# Cutman-RevA.net
KiCad netlist of a schematic drawn in EAGLE
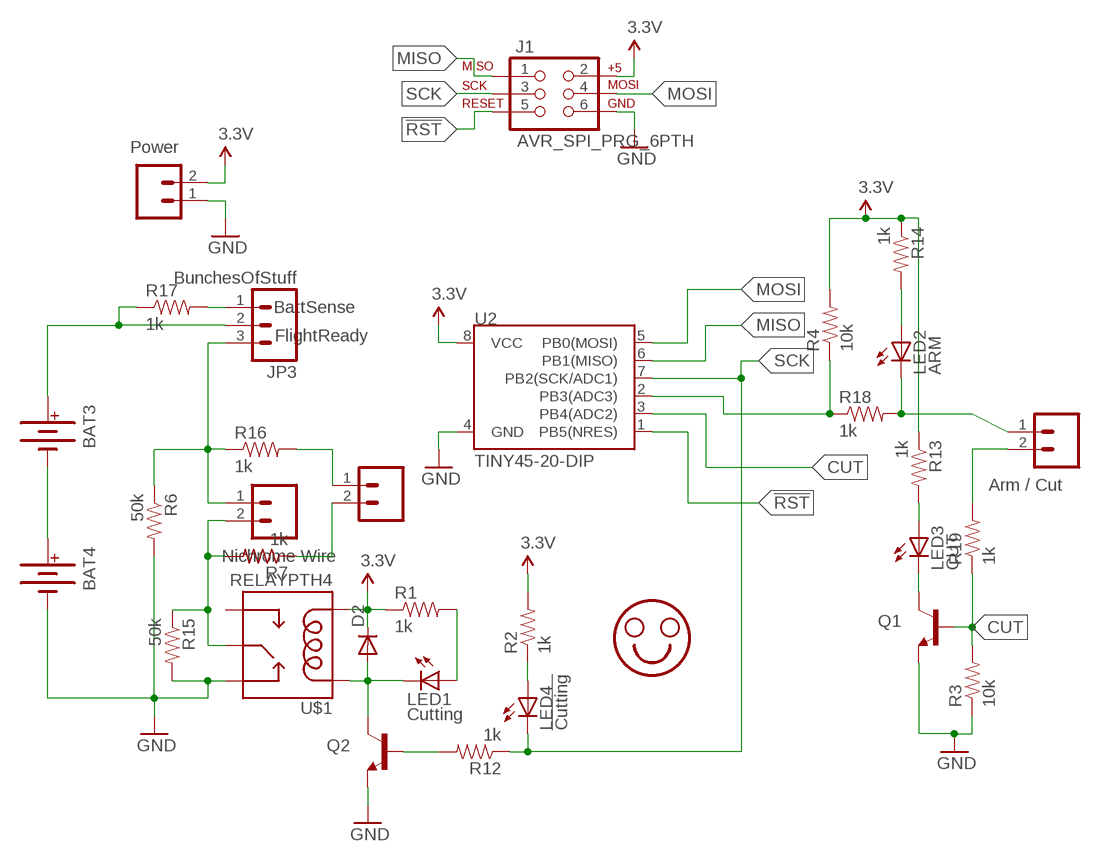
[diagram p0: schematic, sheet 1]

(export (version "E")
  (design (tool "Eeschema 10.0.6"))
  (components
    (comp (ref "BAT3")
      (value "BATTERYAA-KIT")
      (footprint "eagle-import:BATTERY-AA-KIT")
      (libsource (lib "eagle-import") (part "BATTERYAA-KIT"))
    )
    (comp (ref "BAT4")
      (value "BATTERYAA-KIT")
      (footprint "eagle-import:BATTERY-AA-KIT")
      (libsource (lib "eagle-import") (part "BATTERYAA-KIT"))
    )
    (comp (ref "D2")
      (value "DIODEPTH")
      (footprint "eagle-import:DIODE-1N4001")
      (libsource (lib "eagle-import") (part "DIODEPTH"))
    )
    (comp (ref "J1")
      (value "AVR_SPI_PRG_6PTH")
      (footprint "eagle-import:2X3")
      (libsource (lib "eagle-import") (part "AVR_SPI_PRG_6PTH"))
    )
    (comp (ref "JP1")
      (value "NichromeWire")
      (footprint "eagle-import:SCREWTERMINAL-3.5MM-2_LOCK")
      (libsource (lib "eagle-import") (part "M023.5MM_LOCK"))
    )
    (comp (ref "JP2")
      (value "Power")
      (footprint "eagle-import:SCREWTERMINAL-3.5MM-2_LOCK")
      (libsource (lib "eagle-import") (part "M023.5MM_LOCK"))
    )
    (comp (ref "JP3")
      (value "BunchesOfStuff")
      (footprint "eagle-import:SCREWTERMINAL-3.5MM-3")
      (libsource (lib "eagle-import") (part "M03SCREW"))
    )
    (comp (ref "JP4")
      (value "VSense")
      (footprint "eagle-import:SCREWTERMINAL-3.5MM-2_LOCK")
      (libsource (lib "eagle-import") (part "M023.5MM_LOCK"))
    )
    (comp (ref "JP6")
      (value "Arm/Cut")
      (footprint "eagle-import:SCREWTERMINAL-3.5MM-2_LOCK")
      (libsource (lib "eagle-import") (part "M023.5MM_LOCK"))
    )
    (comp (ref "LED1")
      (value "Cutting")
      (footprint "eagle-import:LED5MM")
      (libsource (lib "eagle-import") (part "LED5MM"))
    )
    (comp (ref "LED2")
      (value "ARM")
      (footprint "eagle-import:LED5MM")
      (libsource (lib "eagle-import") (part "LED5MM"))
    )
    (comp (ref "LED3")
      (value "CUT")
      (footprint "eagle-import:LED5MM")
      (libsource (lib "eagle-import") (part "LED5MM"))
    )
    (comp (ref "LED4")
      (value "!Cutting")
      (footprint "eagle-import:LED5MM")
      (libsource (lib "eagle-import") (part "LED5MM"))
    )
    (comp (ref "Q1")
      (value "TRANSISTOR_NPNTO92")
      (footprint "eagle-import:TO-92")
      (libsource (lib "eagle-import") (part "TRANSISTOR_NPNTO92"))
    )
    (comp (ref "Q2")
      (value "TRANSISTOR_NPNTO92")
      (footprint "eagle-import:TO-92")
      (libsource (lib "eagle-import") (part "TRANSISTOR_NPNTO92"))
    )
    (comp (ref "R1")
      (value "1k")
      (footprint "eagle-import:AXIAL-0.3")
      (libsource (lib "eagle-import") (part "RESISTORAXIAL-0.3"))
    )
    (comp (ref "R2")
      (value "1k")
      (footprint "eagle-import:AXIAL-0.3")
      (libsource (lib "eagle-import") (part "RESISTORAXIAL-0.3"))
    )
    (comp (ref "R3")
      (value "10k")
      (footprint "eagle-import:AXIAL-0.3")
      (libsource (lib "eagle-import") (part "RESISTORAXIAL-0.3"))
    )
    (comp (ref "R4")
      (value "10k")
      (footprint "eagle-import:AXIAL-0.3")
      (libsource (lib "eagle-import") (part "RESISTORAXIAL-0.3"))
    )
    (comp (ref "R6")
      (value "50k")
      (footprint "eagle-import:AXIAL-0.3")
      (libsource (lib "eagle-import") (part "RESISTORAXIAL-0.3"))
    )
    (comp (ref "R7")
      (value "1k")
      (footprint "eagle-import:0309V")
      (libsource (lib "eagle-import") (part "R-US_0309/V"))
    )
    (comp (ref "R12")
      (value "1k")
      (footprint "eagle-import:AXIAL-0.3")
      (libsource (lib "eagle-import") (part "RESISTORAXIAL-0.3"))
    )
    (comp (ref "R13")
      (value "1k")
      (footprint "eagle-import:AXIAL-0.3")
      (libsource (lib "eagle-import") (part "RESISTORAXIAL-0.3"))
    )
    (comp (ref "R14")
      (value "1k")
      (footprint "eagle-import:AXIAL-0.3")
      (libsource (lib "eagle-import") (part "RESISTORAXIAL-0.3"))
    )
    (comp (ref "R15")
      (value "50k")
      (footprint "eagle-import:AXIAL-0.3")
      (libsource (lib "eagle-import") (part "RESISTORAXIAL-0.3"))
    )
    (comp (ref "R16")
      (value "1k")
      (footprint "eagle-import:AXIAL-0.3")
      (libsource (lib "eagle-import") (part "RESISTORAXIAL-0.3"))
    )
    (comp (ref "R17")
      (value "1k")
      (footprint "eagle-import:AXIAL-0.3")
      (libsource (lib "eagle-import") (part "RESISTORAXIAL-0.3"))
    )
    (comp (ref "R18")
      (value "1k")
      (footprint "eagle-import:AXIAL-0.3")
      (libsource (lib "eagle-import") (part "RESISTORAXIAL-0.3"))
    )
    (comp (ref "R19")
      (value "1k")
      (footprint "eagle-import:AXIAL-0.3")
      (libsource (lib "eagle-import") (part "RESISTORAXIAL-0.3"))
    )
    (comp (ref "STANDOFF1")
      (value "STAND-OFF")
      (footprint "eagle-import:STAND-OFF")
      (libsource (lib "eagle-import") (part "STAND-OFF"))
    )
    (comp (ref "STANDOFF2")
      (value "STAND-OFF")
      (footprint "eagle-import:STAND-OFF")
      (libsource (lib "eagle-import") (part "STAND-OFF"))
    )
    (comp (ref "U$1")
      (value "RELAYPTH4")
      (footprint "eagle-import:RELAY-JZC")
      (libsource (lib "eagle-import") (part "RELAYPTH4"))
    )
    (comp (ref "U2")
      (value "TINY45-20-DIP")
      (footprint "eagle-import:DIP08")
      (libsource (lib "eagle-import") (part "ATTINY45TINY45-20-DIP"))
    )
  )
  (nets
    (net (code "1") (name "/~{RST}") (class "Default")
      (node (ref "J1") (pin "5") (pinfunction "5_5") (pintype "passive"))
      (node (ref "U2") (pin "1") (pinfunction "PB5(NRES)_1") (pintype "bidirectional"))
    )
    (net (code "2") (name "3.3V") (class "Default")
      (node (ref "D2") (pin "C") (pinfunction "C_C") (pintype "passive"))
      (node (ref "J1") (pin "2") (pinfunction "2_2") (pintype "passive"))
      (node (ref "JP2") (pin "2") (pinfunction "2_2") (pintype "passive"))
      (node (ref "R1") (pin "P$1") (pinfunction "1_P$1") (pintype "passive"))
      (node (ref "R13") (pin "P$1") (pinfunction "1_P$1") (pintype "passive"))
      (node (ref "R14") (pin "P$1") (pinfunction "1_P$1") (pintype "passive"))
      (node (ref "R2") (pin "P$2") (pinfunction "2_P$2") (pintype "passive"))
      (node (ref "R4") (pin "P$2") (pinfunction "2_P$2") (pintype "passive"))
      (node (ref "U$1") (pin "1") (pinfunction "COIL2_1") (pintype "bidirectional"))
      (node (ref "U2") (pin "8") (pinfunction "VCC_8") (pintype "bidirectional"))
    )
    (net (code "3") (name "CUT") (class "Default")
      (node (ref "Q1") (pin "2") (pinfunction "B_2") (pintype "passive"))
      (node (ref "R19") (pin "P$1") (pinfunction "1_P$1") (pintype "passive"))
      (node (ref "R3") (pin "P$2") (pinfunction "2_P$2") (pintype "passive"))
      (node (ref "U2") (pin "3") (pinfunction "PB4(ADC2)_3") (pintype "bidirectional"))
    )
    (net (code "4") (name "GND") (class "Default")
      (node (ref "BAT4") (pin "GND@1") (pinfunction "-_GND@1") (pintype "power_in"))
      (node (ref "BAT4") (pin "GND@2") (pinfunction "-_GND@2") (pintype "power_in"))
      (node (ref "J1") (pin "6") (pinfunction "6_6") (pintype "passive"))
      (node (ref "JP2") (pin "1") (pinfunction "1_1") (pintype "passive"))
      (node (ref "Q1") (pin "1") (pinfunction "E_1") (pintype "passive"))
      (node (ref "Q2") (pin "1") (pinfunction "E_1") (pintype "passive"))
      (node (ref "R15") (pin "P$2") (pinfunction "2_P$2") (pintype "passive"))
      (node (ref "R3") (pin "P$1") (pinfunction "1_P$1") (pintype "passive"))
      (node (ref "R6") (pin "P$2") (pinfunction "2_P$2") (pintype "passive"))
      (node (ref "U$1") (pin "2") (pinfunction "NC_2") (pintype "bidirectional"))
      (node (ref "U2") (pin "4") (pinfunction "GND_4") (pintype "bidirectional"))
    )
    (net (code "5") (name "MISO") (class "Default")
      (node (ref "J1") (pin "1") (pinfunction "1_1") (pintype "passive"))
      (node (ref "U2") (pin "6") (pinfunction "PB1(MISO)_6") (pintype "bidirectional"))
    )
    (net (code "6") (name "MOSI") (class "Default")
      (node (ref "J1") (pin "4") (pinfunction "4_4") (pintype "passive"))
      (node (ref "U2") (pin "5") (pinfunction "PB0(MOSI)_5") (pintype "bidirectional"))
    )
    (net (code "7") (name "Net-(BAT3---PadGND@1)") (class "Default")
      (node (ref "BAT3") (pin "GND@1") (pinfunction "-_GND@1") (pintype "power_in"))
      (node (ref "BAT3") (pin "GND@2") (pinfunction "-_GND@2") (pintype "power_in"))
      (node (ref "BAT4") (pin "PWR@1") (pinfunction "+_PWR@1") (pintype "power_in"))
      (node (ref "BAT4") (pin "PWR@2") (pinfunction "+_PWR@2") (pintype "power_in"))
    )
    (net (code "8") (name "Net-(JP4-Pad2)") (class "Default")
      (node (ref "JP4") (pin "2") (pinfunction "2_2") (pintype "passive"))
      (node (ref "R7") (pin "1") (pinfunction "1_1") (pintype "passive"))
    )
    (net (code "9") (name "Net-(LED1-C)") (class "Default")
      (node (ref "D2") (pin "A") (pinfunction "A_A") (pintype "passive"))
      (node (ref "LED1") (pin "K") (pinfunction "C_K") (pintype "passive"))
      (node (ref "Q2") (pin "3") (pinfunction "C_3") (pintype "passive"))
      (node (ref "U$1") (pin "5") (pinfunction "COIL1_5") (pintype "bidirectional"))
    )
    (net (code "10") (name "Net-(LED2-C)") (class "Default")
      (node (ref "JP6") (pin "1") (pinfunction "1_1") (pintype "passive"))
      (node (ref "LED2") (pin "K") (pinfunction "C_K") (pintype "passive"))
      (node (ref "R18") (pin "P$2") (pinfunction "2_P$2") (pintype "passive"))
    )
    (net (code "11") (name "Net-(LED3-C)") (class "Default")
      (node (ref "LED3") (pin "K") (pinfunction "C_K") (pintype "passive"))
      (node (ref "Q1") (pin "3") (pinfunction "C_3") (pintype "passive"))
    )
    (net (code "12") (name "Net-(Q2-B)") (class "Default")
      (node (ref "Q2") (pin "2") (pinfunction "B_2") (pintype "passive"))
      (node (ref "R12") (pin "P$2") (pinfunction "2_P$2") (pintype "passive"))
    )
    (net (code "13") (name "Net-(R1-2)") (class "Default")
      (node (ref "LED1") (pin "A") (pinfunction "A_A") (pintype "passive"))
      (node (ref "R1") (pin "P$2") (pinfunction "2_P$2") (pintype "passive"))
    )
    (net (code "14") (name "Net-(R2-1)") (class "Default")
      (node (ref "LED4") (pin "A") (pinfunction "A_A") (pintype "passive"))
      (node (ref "R2") (pin "P$1") (pinfunction "1_P$1") (pintype "passive"))
    )
    (net (code "15") (name "Net-(R13-2)") (class "Default")
      (node (ref "LED3") (pin "A") (pinfunction "A_A") (pintype "passive"))
      (node (ref "R13") (pin "P$2") (pinfunction "2_P$2") (pintype "passive"))
    )
    (net (code "16") (name "Net-(R14-2)") (class "Default")
      (node (ref "LED2") (pin "A") (pinfunction "A_A") (pintype "passive"))
      (node (ref "R14") (pin "P$2") (pinfunction "2_P$2") (pintype "passive"))
    )
    (net (code "17") (name "Net-(R15-1)") (class "Default")
      (node (ref "JP1") (pin "2") (pinfunction "2_2") (pintype "passive"))
      (node (ref "R15") (pin "P$1") (pinfunction "1_P$1") (pintype "passive"))
      (node (ref "R7") (pin "2") (pinfunction "2_2") (pintype "passive"))
      (node (ref "U$1") (pin "4") (pinfunction "MAIN_4") (pintype "bidirectional"))
    )
    (net (code "18") (name "Net-(R16-1)") (class "Default")
      (node (ref "JP1") (pin "1") (pinfunction "1_1") (pintype "passive"))
      (node (ref "JP3") (pin "3") (pinfunction "3_3") (pintype "passive"))
      (node (ref "R16") (pin "P$1") (pinfunction "1_P$1") (pintype "passive"))
      (node (ref "R6") (pin "P$1") (pinfunction "1_P$1") (pintype "passive"))
    )
    (net (code "19") (name "Net-(R16-2)") (class "Default")
      (node (ref "JP4") (pin "1") (pinfunction "1_1") (pintype "passive"))
      (node (ref "R16") (pin "P$2") (pinfunction "2_P$2") (pintype "passive"))
    )
    (net (code "20") (name "Net-(R17-1)") (class "Default")
      (node (ref "BAT3") (pin "PWR@1") (pinfunction "+_PWR@1") (pintype "power_in"))
      (node (ref "BAT3") (pin "PWR@2") (pinfunction "+_PWR@2") (pintype "power_in"))
      (node (ref "JP3") (pin "2") (pinfunction "2_2") (pintype "passive"))
      (node (ref "R17") (pin "P$1") (pinfunction "1_P$1") (pintype "passive"))
    )
    (net (code "21") (name "Net-(R17-2)") (class "Default")
      (node (ref "JP3") (pin "1") (pinfunction "1_1") (pintype "passive"))
      (node (ref "R17") (pin "P$2") (pinfunction "2_P$2") (pintype "passive"))
    )
    (net (code "22") (name "Net-(R18-1)") (class "Default")
      (node (ref "R18") (pin "P$1") (pinfunction "1_P$1") (pintype "passive"))
      (node (ref "R4") (pin "P$1") (pinfunction "1_P$1") (pintype "passive"))
      (node (ref "U2") (pin "2") (pinfunction "PB3(ADC3)_2") (pintype "bidirectional"))
    )
    (net (code "23") (name "Net-(R19-2)") (class "Default")
      (node (ref "JP6") (pin "2") (pinfunction "2_2") (pintype "passive"))
      (node (ref "R19") (pin "P$2") (pinfunction "2_P$2") (pintype "passive"))
    )
    (net (code "24") (name "SCK") (class "Default")
      (node (ref "J1") (pin "3") (pinfunction "3_3") (pintype "passive"))
      (node (ref "LED4") (pin "K") (pinfunction "C_K") (pintype "passive"))
      (node (ref "R12") (pin "P$1") (pinfunction "1_P$1") (pintype "passive"))
      (node (ref "U2") (pin "7") (pinfunction "PB2(SCK/ADC1)_7") (pintype "bidirectional"))
    )
    (net (code "25") (name "unconnected-(U$1-NO-Pad3)") (class "Default")
      (node (ref "U$1") (pin "3") (pinfunction "NO_3") (pintype "bidirectional"))
    )
  )
)
